# 2_Relay_module.net
KiCad netlist of a schematic drawn in EAGLE
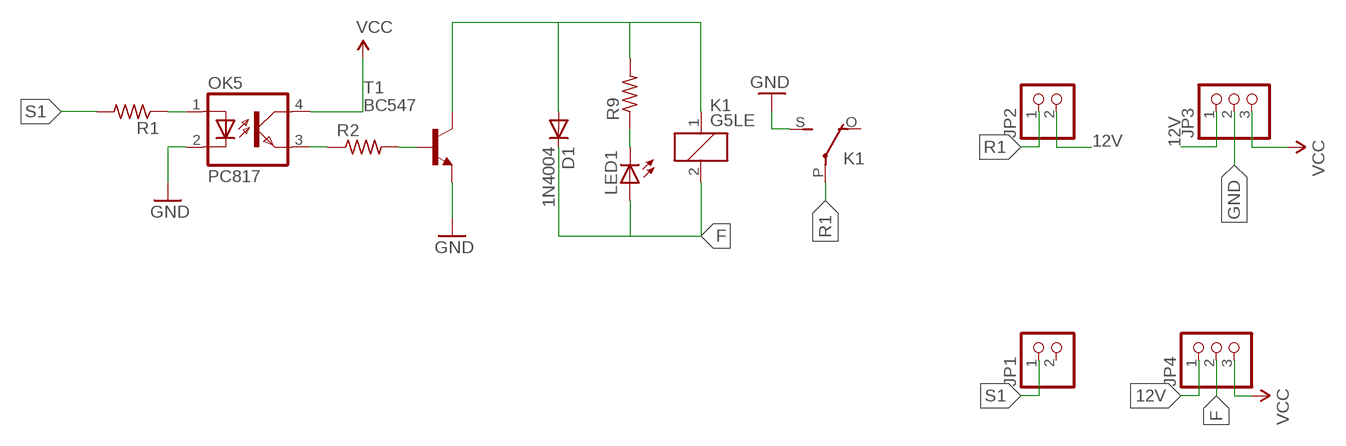
[diagram p0: schematic, sheet 1]

(export (version "E")
  (design (tool "Eeschema 10.0.6"))
  (components
    (comp (ref "D1")
      (value "1N4004")
      (footprint "eagle-import:DO41-10")
      (libsource (lib "eagle-import") (part "1N4004"))
    )
    (comp (ref "JP1")
      (value "PINHD-1X2")
      (footprint "eagle-import:1X02")
      (libsource (lib "eagle-import") (part "PINHD-1X2"))
    )
    (comp (ref "JP2")
      (value "PINHD-1X2")
      (footprint "eagle-import:1X02")
      (libsource (lib "eagle-import") (part "PINHD-1X2"))
    )
    (comp (ref "JP3")
      (value "PINHD-1X3")
      (footprint "eagle-import:1X03")
      (libsource (lib "eagle-import") (part "PINHD-1X3"))
    )
    (comp (ref "JP4")
      (value "PINHD-1X3")
      (footprint "eagle-import:1X03")
      (libsource (lib "eagle-import") (part "PINHD-1X3"))
    )
    (comp (ref "K1")
      (value "G5LE")
      (footprint "eagle-import:G5LE")
      (libsource (lib "eagle-import") (part "G5LE"))
    )
    (comp (ref "LED1")
      (value "LED3MM")
      (footprint "eagle-import:LED3MM")
      (libsource (lib "eagle-import") (part "LED3MM"))
    )
    (comp (ref "OK5")
      (value "PC817")
      (footprint "eagle-import:DIL04")
      (fields (field (name "MPN") "PC817X4J000F"))
      (libsource (lib "eagle-import") (part "PC817"))
    )
    (comp (ref "R1")
      (value "R-US_0204/7")
      (footprint "eagle-import:0204_7")
      (libsource (lib "eagle-import") (part "R-US_0204/7"))
    )
    (comp (ref "R2")
      (value "R-US_0204/7")
      (footprint "eagle-import:0204_7")
      (libsource (lib "eagle-import") (part "R-US_0204/7"))
    )
    (comp (ref "R9")
      (value "R-US_0204/7")
      (footprint "eagle-import:0204_7")
      (libsource (lib "eagle-import") (part "R-US_0204/7"))
    )
    (comp (ref "T1")
      (value "BC547")
      (footprint "eagle-import:TO92")
      (libsource (lib "eagle-import") (part "BC547"))
    )
  )
  (nets
    (net (code "1") (name "12V") (class "Default")
      (node (ref "JP2") (pin "2") (pinfunction "2_2") (pintype "passive"))
      (node (ref "JP3") (pin "1") (pinfunction "1_1") (pintype "passive"))
      (node (ref "JP4") (pin "1") (pinfunction "1_1") (pintype "passive"))
    )
    (net (code "2") (name "F") (class "Default")
      (node (ref "D1") (pin "C") (pinfunction "C_C") (pintype "passive"))
      (node (ref "JP4") (pin "2") (pinfunction "2_2") (pintype "passive"))
      (node (ref "K1") (pin "2") (pinfunction "2_2") (pintype "passive"))
      (node (ref "LED1") (pin "A") (pinfunction "A_A") (pintype "passive"))
    )
    (net (code "3") (name "GND") (class "Default")
      (node (ref "JP3") (pin "2") (pinfunction "2_2") (pintype "passive"))
      (node (ref "K1") (pin "S") (pinfunction "S_S") (pintype "passive"))
      (node (ref "OK5") (pin "2") (pinfunction "C_2") (pintype "passive"))
      (node (ref "T1") (pin "1") (pinfunction "E_1") (pintype "passive"))
    )
    (net (code "4") (name "Net-(LED1-C)") (class "Default")
      (node (ref "LED1") (pin "K") (pinfunction "C_K") (pintype "passive"))
      (node (ref "R9") (pin "1") (pinfunction "1_1") (pintype "passive"))
    )
    (net (code "5") (name "Net-(OK5-A)") (class "Default")
      (node (ref "OK5") (pin "1") (pinfunction "A_1") (pintype "passive"))
      (node (ref "R1") (pin "1") (pinfunction "1_1") (pintype "passive"))
    )
    (net (code "6") (name "Net-(OK5-EMIT)") (class "Default")
      (node (ref "OK5") (pin "3") (pinfunction "EMIT_3") (pintype "passive"))
      (node (ref "R2") (pin "1") (pinfunction "1_1") (pintype "passive"))
    )
    (net (code "7") (name "Net-(T1-B)") (class "Default")
      (node (ref "R2") (pin "2") (pinfunction "2_2") (pintype "passive"))
      (node (ref "T1") (pin "2") (pinfunction "B_2") (pintype "passive"))
    )
    (net (code "8") (name "Net-(T1-C)") (class "Default")
      (node (ref "D1") (pin "A") (pinfunction "A_A") (pintype "passive"))
      (node (ref "K1") (pin "1") (pinfunction "1_1") (pintype "passive"))
      (node (ref "R9") (pin "2") (pinfunction "2_2") (pintype "passive"))
      (node (ref "T1") (pin "3") (pinfunction "C_3") (pintype "passive"))
    )
    (net (code "9") (name "R1") (class "Default")
      (node (ref "JP2") (pin "1") (pinfunction "1_1") (pintype "passive"))
      (node (ref "K1") (pin "P") (pinfunction "P_P") (pintype "passive"))
    )
    (net (code "10") (name "S1") (class "Default")
      (node (ref "JP1") (pin "1") (pinfunction "1_1") (pintype "passive"))
      (node (ref "R1") (pin "2") (pinfunction "2_2") (pintype "passive"))
    )
    (net (code "11") (name "VCC") (class "Default")
      (node (ref "JP3") (pin "3") (pinfunction "3_3") (pintype "passive"))
      (node (ref "JP4") (pin "3") (pinfunction "3_3") (pintype "passive"))
      (node (ref "OK5") (pin "4") (pinfunction "COL_4") (pintype "passive"))
    )
    (net (code "12") (name "unconnected-(JP1-Pad2)") (class "Default")
      (node (ref "JP1") (pin "2") (pinfunction "2_2") (pintype "passive"))
    )
    (net (code "13") (name "unconnected-(K1-PadO)") (class "Default")
      (node (ref "K1") (pin "O") (pinfunction "O_O") (pintype "passive"))
    )
  )
)
